# PCB_Draft_2.net
KiCad netlist of a schematic drawn in EAGLE
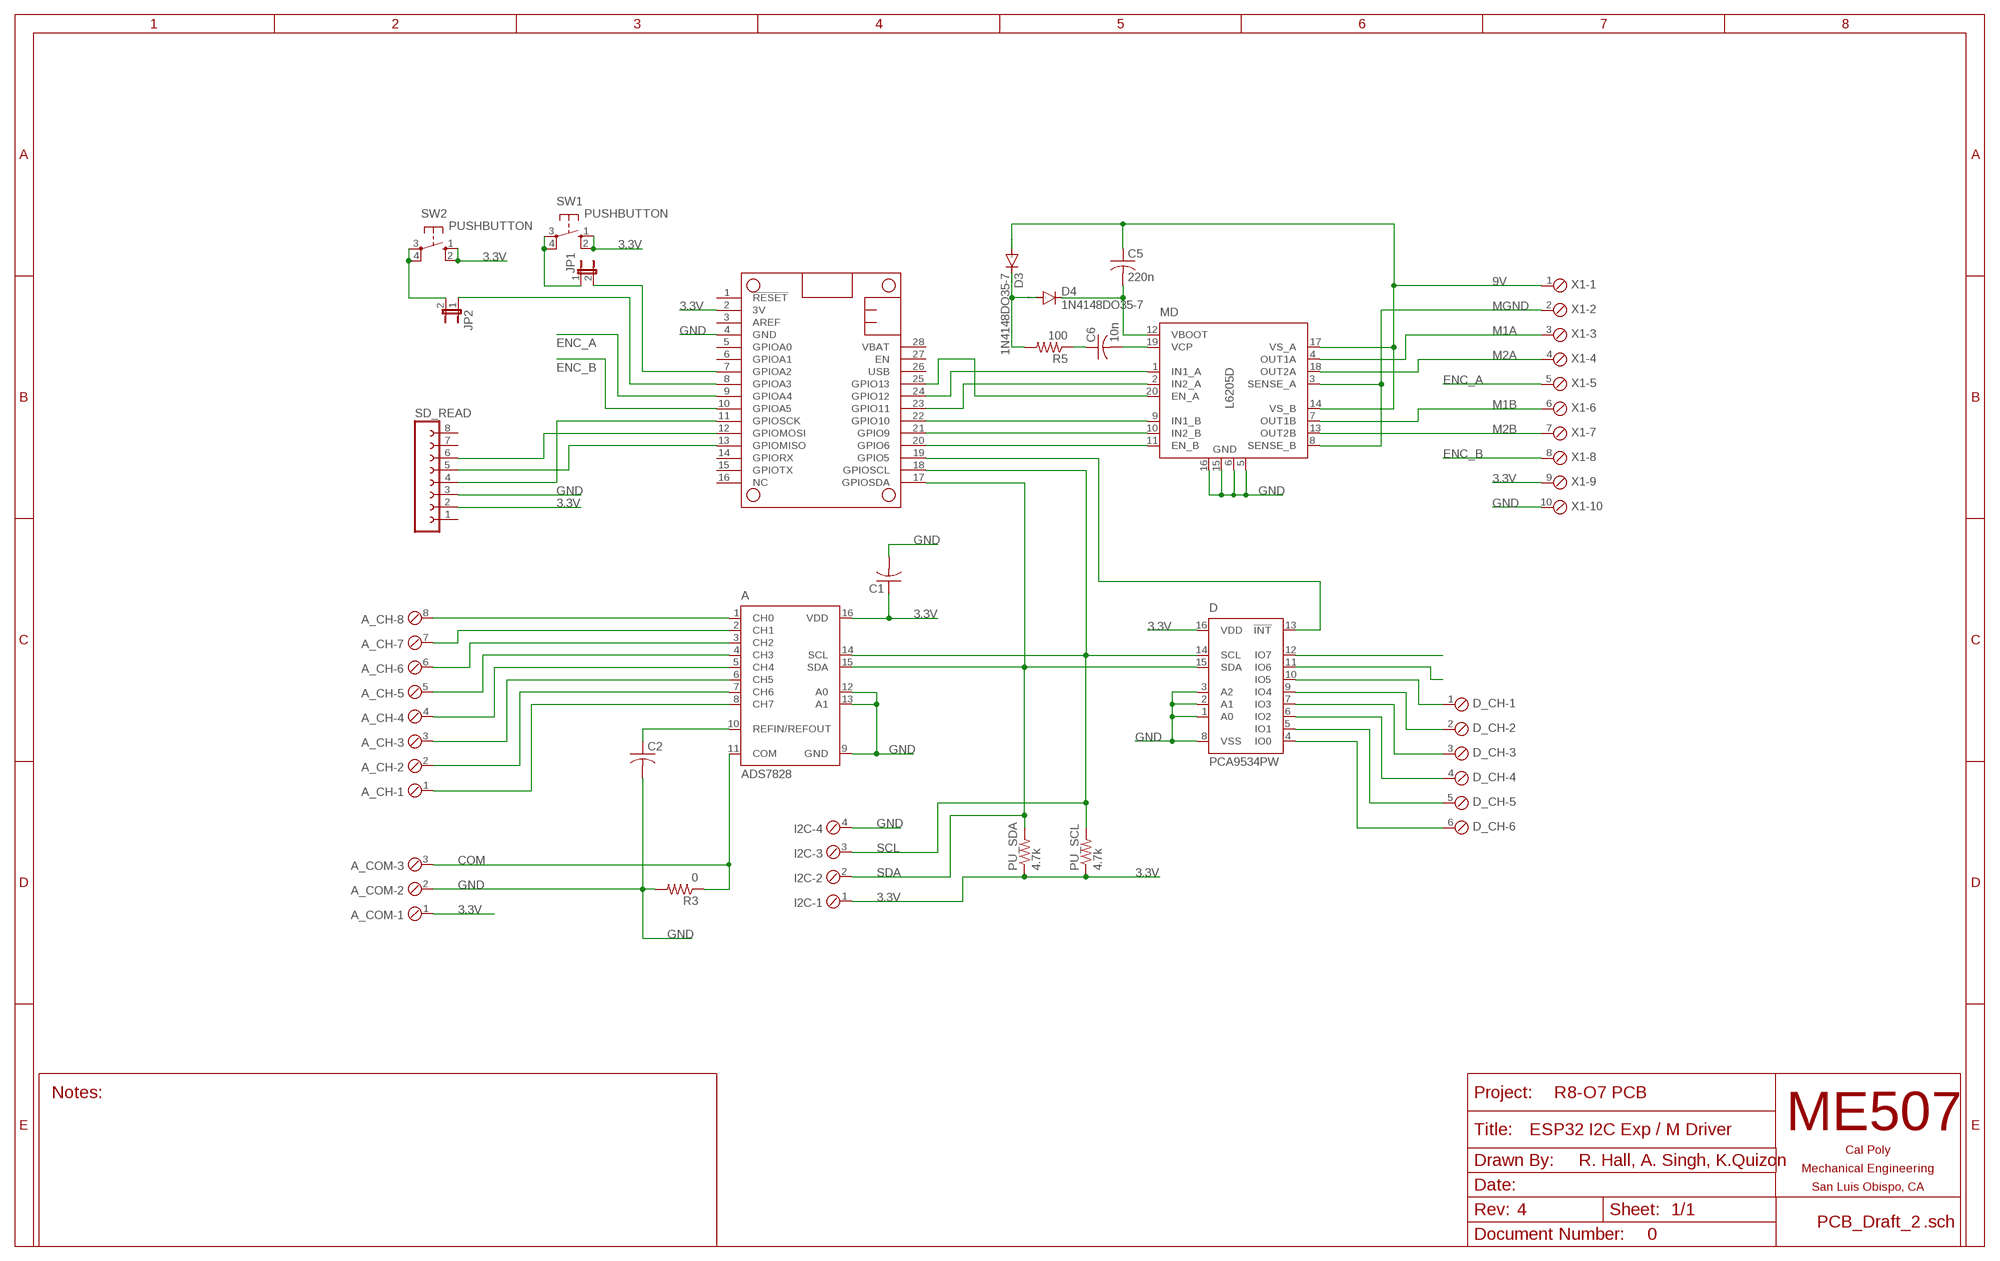
[diagram p0: schematic, sheet 1]

(export (version "E")
  (design (tool "Eeschema 10.0.6"))
  (components
    (comp (ref "A")
      (value "ADS7828")
      (footprint "eagle-import:TSSOP16-PW")
      (fields (field (name "MF") "TEXAS INSTRUMENTS") (field (name "MPN") "ADS7828E/250"))
      (libsource (lib "eagle-import") (part "ADS7828"))
    )
    (comp (ref "A_CH")
      (value "SCREWTERM_8P_254")
      (footprint "eagle-import:8POL254")
      (libsource (lib "eagle-import") (part "SCREWTERM_8P_254"))
    )
    (comp (ref "A_COM")
      (value "SCREWTERM_3P_254")
      (footprint "eagle-import:3POL254")
      (libsource (lib "eagle-import") (part "SCREWTERM_3P_254"))
    )
    (comp (ref "C1")
      (value "C-USC0805")
      (footprint "eagle-import:C0805")
      (libsource (lib "eagle-import") (part "C-USC0805"))
    )
    (comp (ref "C2")
      (value "C-USC0805")
      (footprint "eagle-import:C0805")
      (libsource (lib "eagle-import") (part "C-USC0805"))
    )
    (comp (ref "C5")
      (value "220n")
      (footprint "eagle-import:C0805")
      (libsource (lib "eagle-import") (part "C-USC0805"))
    )
    (comp (ref "C6")
      (value "10n")
      (footprint "eagle-import:C0805")
      (libsource (lib "eagle-import") (part "C-USC0805"))
    )
    (comp (ref "D")
      (value "PCA9534PW")
      (footprint "eagle-import:TSSOP16")
      (libsource (lib "eagle-import") (part "PCA9534PW"))
    )
    (comp (ref "D3")
      (value "1N4148DO35-7")
      (footprint "eagle-import:DO35-7")
      (libsource (lib "eagle-import") (part "1N4148DO35-7"))
    )
    (comp (ref "D4")
      (value "1N4148DO35-7")
      (footprint "eagle-import:DO35-7")
      (libsource (lib "eagle-import") (part "1N4148DO35-7"))
    )
    (comp (ref "D_CH")
      (value "SCREWTERM_6P_254")
      (footprint "eagle-import:6POL254")
      (libsource (lib "eagle-import") (part "SCREWTERM_6P_254"))
    )
    (comp (ref "FTHRWNG")
      (value "FEATHERWINGEXTENDED_BOTH_ENDS")
      (footprint "eagle-import:FEATHERWING")
      (libsource (lib "eagle-import") (part "FEATHERWINGEXTENDED_BOTH_ENDS"))
    )
    (comp (ref "I2C")
      (value "SCREWTERM_4P_254")
      (footprint "eagle-import:4POL254")
      (libsource (lib "eagle-import") (part "SCREWTERM_4P_254"))
    )
    (comp (ref "JP1")
      (value "JP1E")
      (footprint "eagle-import:JP1")
      (libsource (lib "eagle-import") (part "JP1E"))
    )
    (comp (ref "JP2")
      (value "JP1E")
      (footprint "eagle-import:JP1")
      (libsource (lib "eagle-import") (part "JP1E"))
    )
    (comp (ref "MD")
      (value "L6205D")
      (footprint "eagle-import:SO20")
      (libsource (lib "eagle-import") (part "L6205D"))
    )
    (comp (ref "PU_SCL")
      (value "4.7k")
      (footprint "eagle-import:M0805")
      (libsource (lib "eagle-import") (part "R-US_M0805"))
    )
    (comp (ref "PU_SDA")
      (value "4.7k")
      (footprint "eagle-import:M0805")
      (libsource (lib "eagle-import") (part "R-US_M0805"))
    )
    (comp (ref "R3")
      (value "0")
      (footprint "eagle-import:M0805")
      (libsource (lib "eagle-import") (part "R-US_M0805"))
    )
    (comp (ref "R5")
      (value "100")
      (footprint "eagle-import:M0805")
      (libsource (lib "eagle-import") (part "R-US_M0805"))
    )
    (comp (ref "SD_READ")
      (value "FE08-1")
      (footprint "eagle-import:FE08")
      (libsource (lib "eagle-import") (part "FE08-1"))
    )
    (comp (ref "SW1")
      (value "PUSHBUTTON")
      (footprint "eagle-import:B3F-10XX")
      (fields (field (name "MPN") "B3F-1000"))
      (libsource (lib "eagle-import") (part "PUSHBUTTON"))
    )
    (comp (ref "SW2")
      (value "PUSHBUTTON")
      (footprint "eagle-import:B3F-10XX")
      (fields (field (name "MPN") "B3F-1000"))
      (libsource (lib "eagle-import") (part "PUSHBUTTON"))
    )
    (comp (ref "X1")
      (value "SCREWTERM_10P_254")
      (footprint "eagle-import:10POL254")
      (libsource (lib "eagle-import") (part "SCREWTERM_10P_254"))
    )
  )
  (nets
    (net (code "1") (name "/3.3V") (class "Default")
      (node (ref "A") (pin "16") (pinfunction "VDD_16") (pintype "power_in"))
      (node (ref "A_COM") (pin "1") (pinfunction "1_1") (pintype "passive"))
      (node (ref "C1") (pin "1") (pinfunction "1_1") (pintype "passive"))
      (node (ref "D") (pin "16") (pinfunction "VDD_16") (pintype "power_in"))
      (node (ref "FTHRWNG") (pin "2") (pinfunction "3V_2") (pintype "power_in"))
      (node (ref "I2C") (pin "1") (pinfunction "1_1") (pintype "passive"))
      (node (ref "PU_SCL") (pin "1") (pinfunction "1_1") (pintype "passive"))
      (node (ref "PU_SDA") (pin "1") (pinfunction "1_1") (pintype "passive"))
      (node (ref "SD_READ") (pin "2") (pinfunction "2_2") (pintype "passive"))
      (node (ref "SW1") (pin "1") (pinfunction "S_1") (pintype "passive"))
      (node (ref "SW1") (pin "2") (pinfunction "S1_2") (pintype "passive"))
      (node (ref "SW2") (pin "1") (pinfunction "S_1") (pintype "passive"))
      (node (ref "SW2") (pin "2") (pinfunction "S1_2") (pintype "passive"))
      (node (ref "X1") (pin "9") (pinfunction "1_9") (pintype "passive"))
    )
    (net (code "2") (name "/9V") (class "Default")
      (node (ref "C5") (pin "1") (pinfunction "1_1") (pintype "passive"))
      (node (ref "D3") (pin "A") (pinfunction "A_A") (pintype "passive"))
      (node (ref "MD") (pin "14") (pinfunction "VS_B_14") (pintype "power_in"))
      (node (ref "MD") (pin "17") (pinfunction "VS_A_17") (pintype "power_in"))
      (node (ref "X1") (pin "1") (pinfunction "1_1") (pintype "passive"))
    )
    (net (code "3") (name "/COM") (class "Default")
      (node (ref "A") (pin "11") (pinfunction "COM_11") (pintype "input"))
      (node (ref "A_COM") (pin "3") (pinfunction "1_3") (pintype "passive"))
      (node (ref "R3") (pin "1") (pinfunction "1_1") (pintype "passive"))
    )
    (net (code "4") (name "/ENC_A") (class "Default")
      (node (ref "FTHRWNG") (pin "9") (pinfunction "GPIOA4_9") (pintype "bidirectional"))
      (node (ref "X1") (pin "5") (pinfunction "1_5") (pintype "passive"))
    )
    (net (code "5") (name "/ENC_B") (class "Default")
      (node (ref "FTHRWNG") (pin "10") (pinfunction "GPIOA5_10") (pintype "bidirectional"))
      (node (ref "X1") (pin "8") (pinfunction "1_8") (pintype "passive"))
    )
    (net (code "6") (name "/GND") (class "Default")
      (node (ref "A") (pin "12") (pinfunction "A0_12") (pintype "input"))
      (node (ref "A") (pin "13") (pinfunction "A1_13") (pintype "input"))
      (node (ref "A") (pin "9") (pinfunction "GND_9") (pintype "power_in"))
      (node (ref "A_COM") (pin "2") (pinfunction "1_2") (pintype "passive"))
      (node (ref "C1") (pin "2") (pinfunction "2_2") (pintype "passive"))
      (node (ref "C2") (pin "2") (pinfunction "2_2") (pintype "passive"))
      (node (ref "D") (pin "1") (pinfunction "A0_1") (pintype "input"))
      (node (ref "D") (pin "2") (pinfunction "A1_2") (pintype "input"))
      (node (ref "D") (pin "3") (pinfunction "A2_3") (pintype "input"))
      (node (ref "D") (pin "8") (pinfunction "VSS_8") (pintype "power_in"))
      (node (ref "FTHRWNG") (pin "4") (pinfunction "GND_4") (pintype "power_in"))
      (node (ref "I2C") (pin "4") (pinfunction "1_4") (pintype "passive"))
      (node (ref "MD") (pin "15") (pinfunction "GND_15") (pintype "power_in"))
      (node (ref "MD") (pin "16") (pinfunction "GND_16") (pintype "power_in"))
      (node (ref "MD") (pin "5") (pinfunction "GND_5") (pintype "power_in"))
      (node (ref "MD") (pin "6") (pinfunction "GND_6") (pintype "power_in"))
      (node (ref "R3") (pin "2") (pinfunction "2_2") (pintype "passive"))
      (node (ref "SD_READ") (pin "3") (pinfunction "3_3") (pintype "passive"))
      (node (ref "X1") (pin "10") (pinfunction "1_10") (pintype "passive"))
    )
    (net (code "7") (name "/M1A") (class "Default")
      (node (ref "MD") (pin "4") (pinfunction "OUT1A_4") (pintype "output"))
      (node (ref "X1") (pin "3") (pinfunction "1_3") (pintype "passive"))
    )
    (net (code "8") (name "/M1B") (class "Default")
      (node (ref "MD") (pin "7") (pinfunction "OUT1B_7") (pintype "output"))
      (node (ref "X1") (pin "6") (pinfunction "1_6") (pintype "passive"))
    )
    (net (code "9") (name "/M2A") (class "Default")
      (node (ref "MD") (pin "18") (pinfunction "OUT2A_18") (pintype "output"))
      (node (ref "X1") (pin "4") (pinfunction "1_4") (pintype "passive"))
    )
    (net (code "10") (name "/M2B") (class "Default")
      (node (ref "MD") (pin "13") (pinfunction "OUT2B_13") (pintype "output"))
      (node (ref "X1") (pin "7") (pinfunction "1_7") (pintype "passive"))
    )
    (net (code "11") (name "/MGND") (class "Default")
      (node (ref "MD") (pin "3") (pinfunction "SENSE_A_3") (pintype "input"))
      (node (ref "MD") (pin "8") (pinfunction "SENSE_B_8") (pintype "input"))
      (node (ref "X1") (pin "2") (pinfunction "1_2") (pintype "passive"))
    )
    (net (code "12") (name "/SCL") (class "Default")
      (node (ref "A") (pin "14") (pinfunction "SCL_14") (pintype "input"))
      (node (ref "D") (pin "14") (pinfunction "SCL_14") (pintype "input"))
      (node (ref "FTHRWNG") (pin "18") (pinfunction "GPIOSCL_18") (pintype "bidirectional"))
      (node (ref "I2C") (pin "3") (pinfunction "1_3") (pintype "passive"))
      (node (ref "PU_SCL") (pin "2") (pinfunction "2_2") (pintype "passive"))
    )
    (net (code "13") (name "/SDA") (class "Default")
      (node (ref "A") (pin "15") (pinfunction "SDA_15") (pintype "bidirectional"))
      (node (ref "D") (pin "15") (pinfunction "SDA_15") (pintype "bidirectional"))
      (node (ref "FTHRWNG") (pin "17") (pinfunction "GPIOSDA_17") (pintype "bidirectional"))
      (node (ref "I2C") (pin "2") (pinfunction "1_2") (pintype "passive"))
      (node (ref "PU_SDA") (pin "2") (pinfunction "2_2") (pintype "passive"))
    )
    (net (code "14") (name "/USB") (class "Default")
      (node (ref "FTHRWNG") (pin "26") (pinfunction "USB_26") (pintype "power_in"))
    )
    (net (code "15") (name "/VBAT") (class "Default")
      (node (ref "FTHRWNG") (pin "28") (pinfunction "VBAT_28") (pintype "power_in"))
    )
    (net (code "16") (name "Net-(A-CH0)") (class "Default")
      (node (ref "A") (pin "1") (pinfunction "CH0_1") (pintype "input"))
      (node (ref "A_CH") (pin "8") (pinfunction "1_8") (pintype "passive"))
    )
    (net (code "17") (name "Net-(A-CH1)") (class "Default")
      (node (ref "A") (pin "2") (pinfunction "CH1_2") (pintype "input"))
      (node (ref "A_CH") (pin "7") (pinfunction "1_7") (pintype "passive"))
    )
    (net (code "18") (name "Net-(A-CH2)") (class "Default")
      (node (ref "A") (pin "3") (pinfunction "CH2_3") (pintype "input"))
      (node (ref "A_CH") (pin "6") (pinfunction "1_6") (pintype "passive"))
    )
    (net (code "19") (name "Net-(A-CH3)") (class "Default")
      (node (ref "A") (pin "4") (pinfunction "CH3_4") (pintype "input"))
      (node (ref "A_CH") (pin "5") (pinfunction "1_5") (pintype "passive"))
    )
    (net (code "20") (name "Net-(A-CH4)") (class "Default")
      (node (ref "A") (pin "5") (pinfunction "CH4_5") (pintype "input"))
      (node (ref "A_CH") (pin "4") (pinfunction "1_4") (pintype "passive"))
    )
    (net (code "21") (name "Net-(A-CH5)") (class "Default")
      (node (ref "A") (pin "6") (pinfunction "CH5_6") (pintype "input"))
      (node (ref "A_CH") (pin "3") (pinfunction "1_3") (pintype "passive"))
    )
    (net (code "22") (name "Net-(A-CH6)") (class "Default")
      (node (ref "A") (pin "7") (pinfunction "CH6_7") (pintype "input"))
      (node (ref "A_CH") (pin "2") (pinfunction "1_2") (pintype "passive"))
    )
    (net (code "23") (name "Net-(A-CH7)") (class "Default")
      (node (ref "A") (pin "8") (pinfunction "CH7_8") (pintype "input"))
      (node (ref "A_CH") (pin "1") (pinfunction "1_1") (pintype "passive"))
    )
    (net (code "24") (name "Net-(A-REFIN{slash}REFOUT)") (class "Default")
      (node (ref "A") (pin "10") (pinfunction "REFIN/REFOUT_10") (pintype "passive"))
      (node (ref "C2") (pin "1") (pinfunction "1_1") (pintype "passive"))
    )
    (net (code "25") (name "Net-(C6-Pad1)") (class "Default")
      (node (ref "C6") (pin "1") (pinfunction "1_1") (pintype "passive"))
      (node (ref "R5") (pin "1") (pinfunction "1_1") (pintype "passive"))
    )
    (net (code "26") (name "Net-(D-IO0)") (class "Default")
      (node (ref "D") (pin "4") (pinfunction "IO0_4") (pintype "bidirectional"))
      (node (ref "D_CH") (pin "6") (pinfunction "1_6") (pintype "passive"))
    )
    (net (code "27") (name "Net-(D-IO1)") (class "Default")
      (node (ref "D") (pin "5") (pinfunction "IO1_5") (pintype "bidirectional"))
      (node (ref "D_CH") (pin "5") (pinfunction "1_5") (pintype "passive"))
    )
    (net (code "28") (name "Net-(D-IO2)") (class "Default")
      (node (ref "D") (pin "6") (pinfunction "IO2_6") (pintype "bidirectional"))
      (node (ref "D_CH") (pin "4") (pinfunction "1_4") (pintype "passive"))
    )
    (net (code "29") (name "Net-(D-IO3)") (class "Default")
      (node (ref "D") (pin "7") (pinfunction "IO3_7") (pintype "bidirectional"))
      (node (ref "D_CH") (pin "3") (pinfunction "1_3") (pintype "passive"))
    )
    (net (code "30") (name "Net-(D-IO4)") (class "Default")
      (node (ref "D") (pin "9") (pinfunction "IO4_9") (pintype "bidirectional"))
      (node (ref "D_CH") (pin "2") (pinfunction "1_2") (pintype "passive"))
    )
    (net (code "31") (name "Net-(D-IO5)") (class "Default")
      (node (ref "D") (pin "10") (pinfunction "IO5_10") (pintype "bidirectional"))
      (node (ref "D_CH") (pin "1") (pinfunction "1_1") (pintype "passive"))
    )
    (net (code "32") (name "Net-(D-~{INT})") (class "Default")
      (node (ref "D") (pin "13") (pinfunction "~{INT}_13") (pintype "open_collector"))
      (node (ref "FTHRWNG") (pin "19") (pinfunction "GPIO5_19") (pintype "bidirectional"))
    )
    (net (code "33") (name "Net-(D3-PadC)") (class "Default")
      (node (ref "D3") (pin "C") (pinfunction "C_C") (pintype "passive"))
      (node (ref "D4") (pin "A") (pinfunction "A_A") (pintype "passive"))
      (node (ref "R5") (pin "2") (pinfunction "2_2") (pintype "passive"))
    )
    (net (code "34") (name "Net-(FTHRWNG-GPIO6)") (class "Default")
      (node (ref "FTHRWNG") (pin "20") (pinfunction "GPIO6_20") (pintype "bidirectional"))
      (node (ref "MD") (pin "11") (pinfunction "EN_B_11") (pintype "input"))
    )
    (net (code "35") (name "Net-(FTHRWNG-GPIO9)") (class "Default")
      (node (ref "FTHRWNG") (pin "21") (pinfunction "GPIO9_21") (pintype "bidirectional"))
      (node (ref "MD") (pin "10") (pinfunction "IN2_B_10") (pintype "input"))
    )
    (net (code "36") (name "Net-(FTHRWNG-GPIO10)") (class "Default")
      (node (ref "FTHRWNG") (pin "22") (pinfunction "GPIO10_22") (pintype "bidirectional"))
      (node (ref "MD") (pin "9") (pinfunction "IN1_B_9") (pintype "input"))
    )
    (net (code "37") (name "Net-(FTHRWNG-GPIO11)") (class "Default")
      (node (ref "FTHRWNG") (pin "23") (pinfunction "GPIO11_23") (pintype "bidirectional"))
      (node (ref "MD") (pin "2") (pinfunction "IN2_A_2") (pintype "input"))
    )
    (net (code "38") (name "Net-(FTHRWNG-GPIO12)") (class "Default")
      (node (ref "FTHRWNG") (pin "24") (pinfunction "GPIO12_24") (pintype "bidirectional"))
      (node (ref "MD") (pin "1") (pinfunction "IN1_A_1") (pintype "input"))
    )
    (net (code "39") (name "Net-(FTHRWNG-GPIO13)") (class "Default")
      (node (ref "FTHRWNG") (pin "25") (pinfunction "GPIO13_25") (pintype "bidirectional"))
      (node (ref "MD") (pin "20") (pinfunction "EN_A_20") (pintype "input"))
    )
    (net (code "40") (name "Net-(FTHRWNG-GPIOA2)") (class "Default")
      (node (ref "FTHRWNG") (pin "7") (pinfunction "GPIOA2_7") (pintype "bidirectional"))
      (node (ref "JP1") (pin "2") (pinfunction "2_2") (pintype "passive"))
    )
    (net (code "41") (name "Net-(FTHRWNG-GPIOA3)") (class "Default")
      (node (ref "FTHRWNG") (pin "8") (pinfunction "GPIOA3_8") (pintype "bidirectional"))
      (node (ref "JP2") (pin "1") (pinfunction "1_1") (pintype "passive"))
    )
    (net (code "42") (name "Net-(FTHRWNG-GPIOMISO)") (class "Default")
      (node (ref "FTHRWNG") (pin "13") (pinfunction "GPIOMISO_13") (pintype "bidirectional"))
      (node (ref "SD_READ") (pin "5") (pinfunction "5_5") (pintype "passive"))
    )
    (net (code "43") (name "Net-(FTHRWNG-GPIOMOSI)") (class "Default")
      (node (ref "FTHRWNG") (pin "12") (pinfunction "GPIOMOSI_12") (pintype "bidirectional"))
      (node (ref "SD_READ") (pin "6") (pinfunction "6_6") (pintype "passive"))
    )
    (net (code "44") (name "Net-(FTHRWNG-GPIOSCK)") (class "Default")
      (node (ref "FTHRWNG") (pin "11") (pinfunction "GPIOSCK_11") (pintype "bidirectional"))
      (node (ref "SD_READ") (pin "4") (pinfunction "4_4") (pintype "passive"))
    )
    (net (code "45") (name "Net-(MD-VBOOT)") (class "Default")
      (node (ref "C5") (pin "2") (pinfunction "2_2") (pintype "passive"))
      (node (ref "D4") (pin "C") (pinfunction "C_C") (pintype "passive"))
      (node (ref "MD") (pin "12") (pinfunction "VBOOT_12") (pintype "power_in"))
    )
    (net (code "46") (name "Net-(MD-VCP)") (class "Default")
      (node (ref "C6") (pin "2") (pinfunction "2_2") (pintype "passive"))
      (node (ref "MD") (pin "19") (pinfunction "VCP_19") (pintype "power_in"))
    )
    (net (code "47") (name "Net-(SW1-P)") (class "Default")
      (node (ref "JP1") (pin "1") (pinfunction "1_1") (pintype "passive"))
      (node (ref "SW1") (pin "3") (pinfunction "P_3") (pintype "passive"))
      (node (ref "SW1") (pin "4") (pinfunction "P1_4") (pintype "passive"))
    )
    (net (code "48") (name "Net-(SW2-P)") (class "Default")
      (node (ref "JP2") (pin "2") (pinfunction "2_2") (pintype "passive"))
      (node (ref "SW2") (pin "3") (pinfunction "P_3") (pintype "passive"))
      (node (ref "SW2") (pin "4") (pinfunction "P1_4") (pintype "passive"))
    )
    (net (code "49") (name "unconnected-(D-IO6-Pad11)") (class "Default")
      (node (ref "D") (pin "11") (pinfunction "IO6_11") (pintype "bidirectional"))
    )
    (net (code "50") (name "unconnected-(D-IO7-Pad12)") (class "Default")
      (node (ref "D") (pin "12") (pinfunction "IO7_12") (pintype "bidirectional"))
    )
    (net (code "51") (name "unconnected-(FTHRWNG-AREF-Pad3)") (class "Default")
      (node (ref "FTHRWNG") (pin "3") (pinfunction "AREF_3") (pintype "passive"))
    )
    (net (code "52") (name "unconnected-(FTHRWNG-EN-Pad27)") (class "Default")
      (node (ref "FTHRWNG") (pin "27") (pinfunction "EN_27") (pintype "passive"))
    )
    (net (code "53") (name "unconnected-(FTHRWNG-GPIOA0-Pad5)") (class "Default")
      (node (ref "FTHRWNG") (pin "5") (pinfunction "GPIOA0_5") (pintype "bidirectional"))
    )
    (net (code "54") (name "unconnected-(FTHRWNG-GPIOA1-Pad6)") (class "Default")
      (node (ref "FTHRWNG") (pin "6") (pinfunction "GPIOA1_6") (pintype "bidirectional"))
    )
    (net (code "55") (name "unconnected-(FTHRWNG-GPIORX-Pad14)") (class "Default")
      (node (ref "FTHRWNG") (pin "14") (pinfunction "GPIORX_14") (pintype "bidirectional"))
    )
    (net (code "56") (name "unconnected-(FTHRWNG-GPIOTX-Pad15)") (class "Default")
      (node (ref "FTHRWNG") (pin "15") (pinfunction "GPIOTX_15") (pintype "bidirectional"))
    )
    (net (code "57") (name "unconnected-(FTHRWNG-NC-Pad16)") (class "Default")
      (node (ref "FTHRWNG") (pin "16") (pinfunction "NC_16") (pintype "passive"))
    )
    (net (code "58") (name "unconnected-(FTHRWNG-~{RESET}-Pad1)") (class "Default")
      (node (ref "FTHRWNG") (pin "1") (pinfunction "~{RESET}_1") (pintype "input"))
    )
    (net (code "59") (name "unconnected-(SD_READ-Pad1)") (class "Default")
      (node (ref "SD_READ") (pin "1") (pinfunction "1_1") (pintype "passive"))
    )
    (net (code "60") (name "unconnected-(SD_READ-Pad7)") (class "Default")
      (node (ref "SD_READ") (pin "7") (pinfunction "7_7") (pintype "passive"))
    )
    (net (code "61") (name "unconnected-(SD_READ-Pad8)") (class "Default")
      (node (ref "SD_READ") (pin "8") (pinfunction "8_8") (pintype "passive"))
    )
  )
)
